# femtoduino.net
KiCad netlist of a schematic drawn in EAGLE
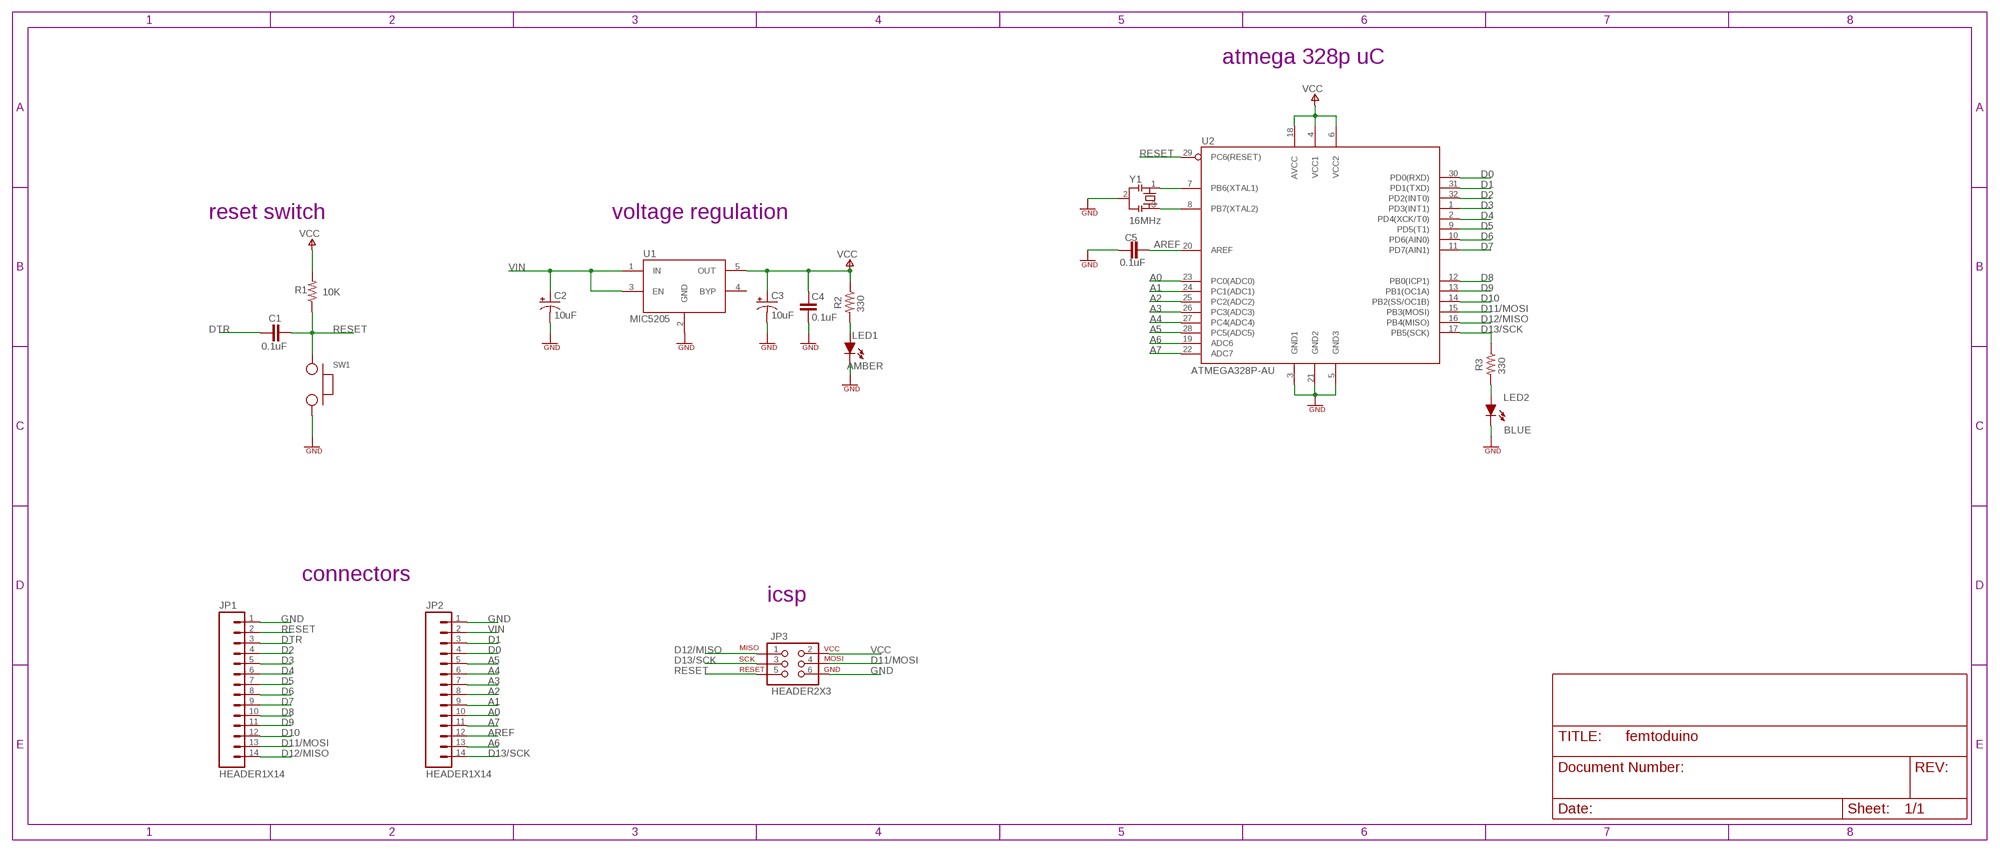
[diagram p0: schematic, sheet 1]

(export (version "E")
  (design (tool "Eeschema 10.0.6"))
  (components
    (comp (ref "C1")
      (value "0.1uF")
      (footprint "eagle-import:SMD0603")
      (libsource (lib "eagle-import") (part "CAP_0603"))
    )
    (comp (ref "C2")
      (value "10uF")
      (footprint "eagle-import:EIA3216")
      (libsource (lib "eagle-import") (part "CAP_TANT"))
    )
    (comp (ref "C3")
      (value "10uF")
      (footprint "eagle-import:EIA3216")
      (libsource (lib "eagle-import") (part "CAP_TANT"))
    )
    (comp (ref "C4")
      (value "0.1uF")
      (footprint "eagle-import:SMD0603")
      (libsource (lib "eagle-import") (part "CAP_0603"))
    )
    (comp (ref "C5")
      (value "0.1uF")
      (footprint "eagle-import:SMD0603")
      (libsource (lib "eagle-import") (part "CAP_0603"))
    )
    (comp (ref "JP1")
      (value "HEADER1X14")
      (footprint "eagle-import:1X14")
      (libsource (lib "eagle-import") (part "HEADER1X14"))
    )
    (comp (ref "JP2")
      (value "HEADER1X14")
      (footprint "eagle-import:1X14")
      (libsource (lib "eagle-import") (part "HEADER1X14"))
    )
    (comp (ref "JP3")
      (value "HEADER2X3")
      (footprint "eagle-import:2X3")
      (libsource (lib "eagle-import") (part "HEADER2X3"))
    )
    (comp (ref "LED1")
      (value "AMBER")
      (footprint "eagle-import:LED_0603")
      (libsource (lib "eagle-import") (part "LED_0603"))
    )
    (comp (ref "LED2")
      (value "BLUE")
      (footprint "eagle-import:LED_0603")
      (libsource (lib "eagle-import") (part "LED_0603"))
    )
    (comp (ref "R1")
      (value "10K")
      (footprint "eagle-import:SMD0603")
      (libsource (lib "eagle-import") (part "RES_0603"))
    )
    (comp (ref "R2")
      (value "330")
      (footprint "eagle-import:SMD0603")
      (libsource (lib "eagle-import") (part "RES_0603"))
    )
    (comp (ref "R3")
      (value "330")
      (footprint "eagle-import:SMD0603")
      (libsource (lib "eagle-import") (part "RES_0603"))
    )
    (comp (ref "SW1")
      (value "SWITCH")
      (footprint "eagle-import:SWITCH-SPST")
      (libsource (lib "eagle-import") (part "SWITCH"))
    )
    (comp (ref "U1")
      (value "MIC5205")
      (footprint "eagle-import:SOT23-5")
      (libsource (lib "eagle-import") (part "MIC5205"))
    )
    (comp (ref "U2")
      (value "ATMEGA328P-AU")
      (footprint "eagle-import:TQFP32")
      (libsource (lib "eagle-import") (part "ATMEGA328P-AU"))
    )
    (comp (ref "Y1")
      (value "16MHz")
      (footprint "eagle-import:CSTCE")
      (libsource (lib "eagle-import") (part "CSTCE"))
    )
  )
  (nets
    (net (code "1") (name "/A0") (class "Default")
      (node (ref "JP2") (pin "10") (pinfunction "10_10") (pintype "passive"))
      (node (ref "U2") (pin "23") (pinfunction "PC0(ADC0)_23") (pintype "bidirectional"))
    )
    (net (code "2") (name "/A1") (class "Default")
      (node (ref "JP2") (pin "9") (pinfunction "9_9") (pintype "passive"))
      (node (ref "U2") (pin "24") (pinfunction "PC1(ADC1)_24") (pintype "bidirectional"))
    )
    (net (code "3") (name "/A2") (class "Default")
      (node (ref "JP2") (pin "8") (pinfunction "8_8") (pintype "passive"))
      (node (ref "U2") (pin "25") (pinfunction "PC2(ADC2)_25") (pintype "bidirectional"))
    )
    (net (code "4") (name "/A3") (class "Default")
      (node (ref "JP2") (pin "7") (pinfunction "7_7") (pintype "passive"))
      (node (ref "U2") (pin "26") (pinfunction "PC3(ADC3)_26") (pintype "bidirectional"))
    )
    (net (code "5") (name "/A4") (class "Default")
      (node (ref "JP2") (pin "6") (pinfunction "6_6") (pintype "passive"))
      (node (ref "U2") (pin "27") (pinfunction "PC4(ADC4)_27") (pintype "bidirectional"))
    )
    (net (code "6") (name "/A5") (class "Default")
      (node (ref "JP2") (pin "5") (pinfunction "5_5") (pintype "passive"))
      (node (ref "U2") (pin "28") (pinfunction "PC5(ADC5)_28") (pintype "bidirectional"))
    )
    (net (code "7") (name "/A6") (class "Default")
      (node (ref "JP2") (pin "13") (pinfunction "13_13") (pintype "passive"))
      (node (ref "U2") (pin "19") (pinfunction "ADC6_19") (pintype "bidirectional"))
    )
    (net (code "8") (name "/A7") (class "Default")
      (node (ref "JP2") (pin "11") (pinfunction "11_11") (pintype "passive"))
      (node (ref "U2") (pin "22") (pinfunction "ADC7_22") (pintype "bidirectional"))
    )
    (net (code "9") (name "/AREF") (class "Default")
      (node (ref "C5") (pin "1") (pinfunction "1_1") (pintype "passive"))
      (node (ref "JP2") (pin "12") (pinfunction "12_12") (pintype "passive"))
      (node (ref "U2") (pin "20") (pinfunction "AREF_20") (pintype "bidirectional"))
    )
    (net (code "10") (name "/D0") (class "Default")
      (node (ref "JP2") (pin "4") (pinfunction "4_4") (pintype "passive"))
      (node (ref "U2") (pin "30") (pinfunction "PD0(RXD)_30") (pintype "bidirectional"))
    )
    (net (code "11") (name "/D1") (class "Default")
      (node (ref "JP2") (pin "3") (pinfunction "3_3") (pintype "passive"))
      (node (ref "U2") (pin "31") (pinfunction "PD1(TXD)_31") (pintype "bidirectional"))
    )
    (net (code "12") (name "/D2") (class "Default")
      (node (ref "JP1") (pin "4") (pinfunction "4_4") (pintype "passive"))
      (node (ref "U2") (pin "32") (pinfunction "PD2(INT0)_32") (pintype "bidirectional"))
    )
    (net (code "13") (name "/D3") (class "Default")
      (node (ref "JP1") (pin "5") (pinfunction "5_5") (pintype "passive"))
      (node (ref "U2") (pin "1") (pinfunction "PD3(INT1)_1") (pintype "bidirectional"))
    )
    (net (code "14") (name "/D4") (class "Default")
      (node (ref "JP1") (pin "6") (pinfunction "6_6") (pintype "passive"))
      (node (ref "U2") (pin "2") (pinfunction "PD4(XCK/T0)_2") (pintype "bidirectional"))
    )
    (net (code "15") (name "/D5") (class "Default")
      (node (ref "JP1") (pin "7") (pinfunction "7_7") (pintype "passive"))
      (node (ref "U2") (pin "9") (pinfunction "PD5(T1)_9") (pintype "bidirectional"))
    )
    (net (code "16") (name "/D6") (class "Default")
      (node (ref "JP1") (pin "8") (pinfunction "8_8") (pintype "passive"))
      (node (ref "U2") (pin "10") (pinfunction "PD6(AIN0)_10") (pintype "bidirectional"))
    )
    (net (code "17") (name "/D7") (class "Default")
      (node (ref "JP1") (pin "9") (pinfunction "9_9") (pintype "passive"))
      (node (ref "U2") (pin "11") (pinfunction "PD7(AIN1)_11") (pintype "bidirectional"))
    )
    (net (code "18") (name "/D8") (class "Default")
      (node (ref "JP1") (pin "10") (pinfunction "10_10") (pintype "passive"))
      (node (ref "U2") (pin "12") (pinfunction "PB0(ICP1)_12") (pintype "bidirectional"))
    )
    (net (code "19") (name "/D9") (class "Default")
      (node (ref "JP1") (pin "11") (pinfunction "11_11") (pintype "passive"))
      (node (ref "U2") (pin "13") (pinfunction "PB1(OC1A)_13") (pintype "bidirectional"))
    )
    (net (code "20") (name "/D10") (class "Default")
      (node (ref "JP1") (pin "12") (pinfunction "12_12") (pintype "passive"))
      (node (ref "U2") (pin "14") (pinfunction "PB2(SS/OC1B)_14") (pintype "bidirectional"))
    )
    (net (code "21") (name "/D11{slash}MOSI") (class "Default")
      (node (ref "JP1") (pin "13") (pinfunction "13_13") (pintype "passive"))
      (node (ref "JP3") (pin "4") (pinfunction "4_4") (pintype "passive"))
      (node (ref "U2") (pin "15") (pinfunction "PB3(MOSI)_15") (pintype "bidirectional"))
    )
    (net (code "22") (name "/D12{slash}MISO") (class "Default")
      (node (ref "JP1") (pin "14") (pinfunction "14_14") (pintype "passive"))
      (node (ref "JP3") (pin "1") (pinfunction "1_1") (pintype "passive"))
      (node (ref "U2") (pin "16") (pinfunction "PB4(MISO)_16") (pintype "bidirectional"))
    )
    (net (code "23") (name "/D13{slash}SCK") (class "Default")
      (node (ref "JP2") (pin "14") (pinfunction "14_14") (pintype "passive"))
      (node (ref "JP3") (pin "3") (pinfunction "3_3") (pintype "passive"))
      (node (ref "R3") (pin "1") (pinfunction "1_1") (pintype "passive"))
      (node (ref "U2") (pin "17") (pinfunction "PB5(SCK)_17") (pintype "bidirectional"))
    )
    (net (code "24") (name "/DTR") (class "Default")
      (node (ref "C1") (pin "1") (pinfunction "1_1") (pintype "passive"))
      (node (ref "JP1") (pin "3") (pinfunction "3_3") (pintype "passive"))
    )
    (net (code "25") (name "/RESET") (class "Default")
      (node (ref "C1") (pin "2") (pinfunction "2_2") (pintype "passive"))
      (node (ref "JP1") (pin "2") (pinfunction "2_2") (pintype "passive"))
      (node (ref "JP3") (pin "5") (pinfunction "5_5") (pintype "passive"))
      (node (ref "R1") (pin "1") (pinfunction "1_1") (pintype "passive"))
      (node (ref "SW1") (pin "1") (pinfunction "1_1") (pintype "bidirectional"))
      (node (ref "U2") (pin "29") (pinfunction "PC6(RESET)_29") (pintype "bidirectional"))
    )
    (net (code "26") (name "/VIN") (class "Default")
      (node (ref "C2") (pin "A") (pinfunction "+_A") (pintype "passive"))
      (node (ref "JP2") (pin "2") (pinfunction "2_2") (pintype "passive"))
      (node (ref "U1") (pin "1") (pinfunction "IN_1") (pintype "bidirectional"))
      (node (ref "U1") (pin "3") (pinfunction "EN_3") (pintype "bidirectional"))
    )
    (net (code "27") (name "GND") (class "Default")
      (node (ref "C2") (pin "C") (pinfunction "-_C") (pintype "passive"))
      (node (ref "C3") (pin "C") (pinfunction "-_C") (pintype "passive"))
      (node (ref "C4") (pin "2") (pinfunction "2_2") (pintype "passive"))
      (node (ref "C5") (pin "2") (pinfunction "2_2") (pintype "passive"))
      (node (ref "JP1") (pin "1") (pinfunction "1_1") (pintype "passive"))
      (node (ref "JP2") (pin "1") (pinfunction "1_1") (pintype "passive"))
      (node (ref "JP3") (pin "6") (pinfunction "6_6") (pintype "passive"))
      (node (ref "LED1") (pin "C") (pinfunction "C_C") (pintype "passive"))
      (node (ref "LED2") (pin "C") (pinfunction "C_C") (pintype "passive"))
      (node (ref "SW1") (pin "2") (pinfunction "2_2") (pintype "bidirectional"))
      (node (ref "U1") (pin "2") (pinfunction "GND_2") (pintype "bidirectional"))
      (node (ref "U2") (pin "21") (pinfunction "GND2_21") (pintype "bidirectional"))
      (node (ref "U2") (pin "3") (pinfunction "GND1_3") (pintype "bidirectional"))
      (node (ref "U2") (pin "5") (pinfunction "GND3_5") (pintype "bidirectional"))
      (node (ref "Y1") (pin "2") (pinfunction "2_2") (pintype "passive"))
    )
    (net (code "28") (name "Net-(LED1-PadA)") (class "Default")
      (node (ref "LED1") (pin "A") (pinfunction "A_A") (pintype "passive"))
      (node (ref "R2") (pin "2") (pinfunction "2_2") (pintype "passive"))
    )
    (net (code "29") (name "Net-(LED2-PadA)") (class "Default")
      (node (ref "LED2") (pin "A") (pinfunction "A_A") (pintype "passive"))
      (node (ref "R3") (pin "2") (pinfunction "2_2") (pintype "passive"))
    )
    (net (code "30") (name "Net-(U2-PB6(XTAL1))") (class "Default")
      (node (ref "U2") (pin "7") (pinfunction "PB6(XTAL1)_7") (pintype "bidirectional"))
      (node (ref "Y1") (pin "1") (pinfunction "1_1") (pintype "passive"))
    )
    (net (code "31") (name "Net-(U2-PB7(XTAL2))") (class "Default")
      (node (ref "U2") (pin "8") (pinfunction "PB7(XTAL2)_8") (pintype "bidirectional"))
      (node (ref "Y1") (pin "3") (pinfunction "3_3") (pintype "passive"))
    )
    (net (code "32") (name "VCC") (class "Default")
      (node (ref "C3") (pin "A") (pinfunction "+_A") (pintype "passive"))
      (node (ref "C4") (pin "1") (pinfunction "1_1") (pintype "passive"))
      (node (ref "JP3") (pin "2") (pinfunction "2_2") (pintype "passive"))
      (node (ref "R1") (pin "2") (pinfunction "2_2") (pintype "passive"))
      (node (ref "R2") (pin "1") (pinfunction "1_1") (pintype "passive"))
      (node (ref "U1") (pin "5") (pinfunction "OUT_5") (pintype "bidirectional"))
      (node (ref "U2") (pin "18") (pinfunction "AVCC_18") (pintype "bidirectional"))
      (node (ref "U2") (pin "4") (pinfunction "VCC1_4") (pintype "bidirectional"))
      (node (ref "U2") (pin "6") (pinfunction "VCC2_6") (pintype "bidirectional"))
    )
    (net (code "33") (name "unconnected-(U1-BYP-Pad4)") (class "Default")
      (node (ref "U1") (pin "4") (pinfunction "BYP_4") (pintype "passive"))
    )
  )
)
